# f401ccu6_w25q64_20210612.net
KiCad netlist of a schematic drawn in Altium Designer
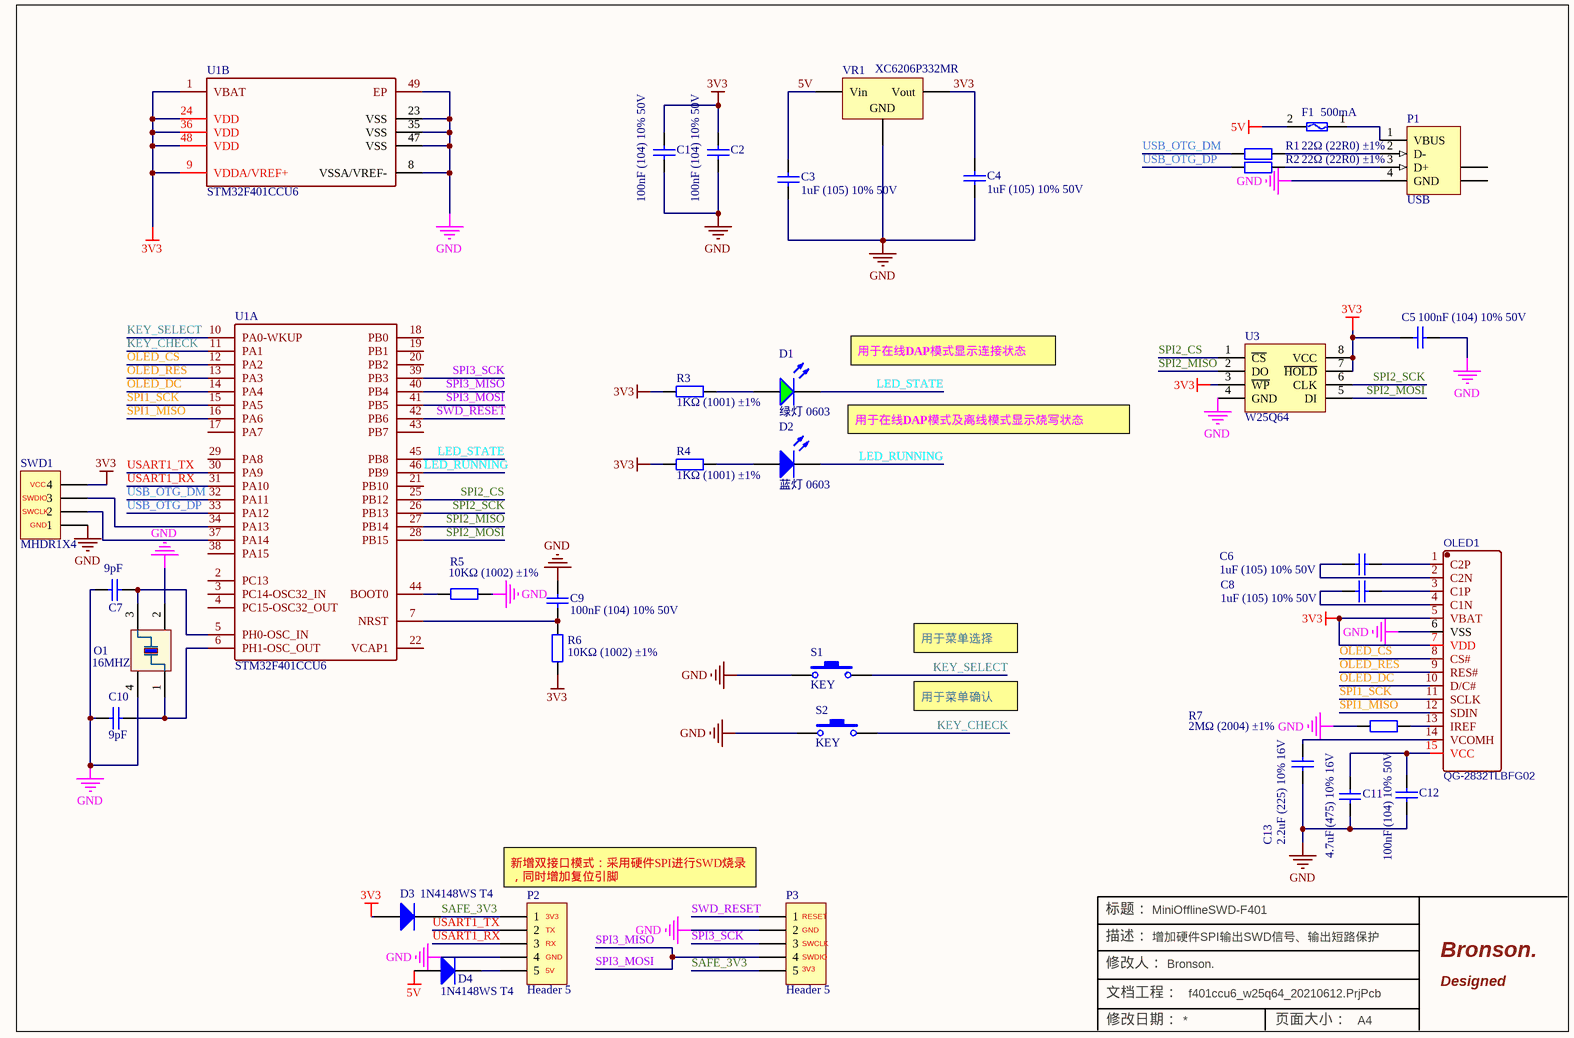
[diagram p0: f401ccu6_w25q64_20210612.SchDoc]

(export (version "E")
  (design (tool "Eeschema 10.0.6"))
  (components
    (comp (ref "C1")
      (value "100nF (104) 10% 50V")
      (footprint "pcblib201812:0805L")
      (description "贴片电容")
      (libsource (lib "Miscellaneous Devices LC") (part "0603 100nF (104) 10% 50V"))
    )
    (comp (ref "C2")
      (value "100nF (104) 10% 50V")
      (footprint "C0603")
      (description "贴片电容")
      (libsource (lib "Miscellaneous Devices LC") (part "0603 100nF (104) 10% 50V"))
    )
    (comp (ref "C3")
      (value "1uF (105) 10% 50V")
      (footprint "pcblib201812:0805L")
      (description "贴片电容")
      (libsource (lib "Miscellaneous Devices LC") (part "0603 1uF (105) 10% 50V"))
    )
    (comp (ref "C4")
      (value "1uF (105) 10% 50V")
      (footprint "pcblib201812:C0603")
      (description "贴片电容")
      (libsource (lib "Miscellaneous Devices LC") (part "0603 1uF (105) 10% 50V"))
    )
    (comp (ref "C5")
      (value "100nF (104) 10% 50V")
      (footprint "pcblib201812:C0603")
      (description "贴片电容")
      (libsource (lib "Miscellaneous Devices LC") (part "0603 100nF (104) 10% 50V"))
    )
    (comp (ref "C6")
      (value "1uF (105) 10% 50V")
      (footprint "pcblib201812:C0603")
      (description "贴片电容")
      (libsource (lib "Miscellaneous Devices LC") (part "0603 1uF (105) 10% 50V"))
    )
    (comp (ref "C7")
      (value "9pF")
      (footprint "pcblib201812:C0603")
      (description "贴片电容")
      (libsource (lib "Miscellaneous Devices LC") (part "0603 22pF (220) 5% 50V"))
    )
    (comp (ref "C8")
      (value "1uF (105) 10% 50V")
      (footprint "pcblib201812:C0603")
      (description "贴片电容")
      (libsource (lib "Miscellaneous Devices LC") (part "0603 1uF (105) 10% 50V"))
    )
    (comp (ref "C9")
      (value "100nF (104) 10% 50V")
      (footprint "pcblib201812:C0603")
      (description "贴片电容")
      (libsource (lib "Miscellaneous Devices LC") (part "0603 100nF (104) 10% 50V"))
    )
    (comp (ref "C10")
      (value "9pF")
      (footprint "pcblib201812:C0603")
      (description "贴片电容")
      (libsource (lib "Miscellaneous Devices LC") (part "0603 22pF (220) 5% 50V"))
    )
    (comp (ref "C11")
      (value "4.7uF (475) 10% 16V")
      (footprint "pcblib201812:C0603")
      (description "贴片电容")
      (libsource (lib "Miscellaneous Devices LC") (part "0603 4.7uF (475) 10% 16V"))
    )
    (comp (ref "C12")
      (value "100nF (104) 10% 50V")
      (footprint "pcblib201812:C0603")
      (description "贴片电容")
      (libsource (lib "Miscellaneous Devices LC") (part "0603 100nF (104) 10% 50V"))
    )
    (comp (ref "C13")
      (value "2.2uF (225) 10% 16V")
      (footprint "pcblib201812:C0603")
      (description "贴片电容")
      (libsource (lib "Miscellaneous Devices LC") (part "0603 2.2uF (225) 10% 16V"))
    )
    (comp (ref "D1")
      (value "绿灯 0603")
      (footprint "pcblib201812:LED_0603_GREEN")
      (description "发光二极管")
      (libsource (lib "Miscellaneous Devices LC") (part "0603 绿灯"))
    )
    (comp (ref "D2")
      (value "蓝灯 0603")
      (footprint "pcblib201812:LED_0603_BLUE")
      (description "发光二极管")
      (libsource (lib "Miscellaneous Devices LC") (part "0603 蓝灯"))
    )
    (comp (ref "D3")
      (value "1N4148WS T4")
      (footprint "SOD-323")
      (description "二极管")
      (libsource (lib "Miscellaneous Devices LC") (part "SOD-323 1N4148WS T4"))
    )
    (comp (ref "D4")
      (value "1N4148WS T4")
      (footprint "SOD-323")
      (description "二极管")
      (libsource (lib "Miscellaneous Devices LC") (part "SOD-323 1N4148WS T4"))
    )
    (comp (ref "F1")
      (value "500mA")
      (footprint "0603")
      (description "保险丝，熔断丝")
      (libsource (lib "Free Documents") (part "FUSE"))
    )
    (comp (ref "O1")
      (value "16MHZ")
      (footprint "pcblib201812:OSC 3225-4P")
      (description "OSC")
      (libsource (lib "altium-import") (part "root_1_OSC_"))
    )
    (comp (ref "OLED1")
      (value "QG-2832TLBFG02")
      (footprint "0.91-OLED")
      (fields (field (name "BOM_SUPPLIER PART") "C91220") (field (name "CONTRIBUTOR") "LCSC"))
      (libsource (lib "0.91-oled") (part "0.91-OLED"))
    )
    (comp (ref "P1")
      (value "USB")
      (footprint "f103ret6_w25q64_20200910:USB_A/P_B")
      (description "USB 1.1, Right Angle, SMT, A Type, Plug, 4 Position, Natural")
      (fields (field (name "PUBLISHER") "Altium Limited"))
      (libsource (lib "AMP Serial Bus USB") (part "1470695-2"))
    )
    (comp (ref "P2")
      (value "Header 5")
      (footprint "5PinHeader:PinHeader_5")
      (description "Header, 5-Pin")
      (fields (field (name "PUBLISHER") "Altium Limited"))
      (libsource (lib "Miscellaneous Connectors") (part "Header 5"))
    )
    (comp (ref "P3")
      (value "Header 5")
      (footprint "5PinHeader:PinHeader_5")
      (description "Header, 5-Pin")
      (fields (field (name "PUBLISHER") "Altium Limited"))
      (libsource (lib "Miscellaneous Connectors") (part "Header 5"))
    )
    (comp (ref "R1")
      (value "22Ω (22R0) ±1%")
      (footprint "pcblib201812:RES0603")
      (description "贴片电阻")
      (libsource (lib "Miscellaneous Devices LC") (part "0603 22Ω (22R0) 1%"))
    )
    (comp (ref "R2")
      (value "22Ω (22R0) ±1%")
      (footprint "pcblib201812:RES0603")
      (description "贴片电阻")
      (libsource (lib "Miscellaneous Devices LC") (part "0603 22Ω (22R0) 1%"))
    )
    (comp (ref "R3")
      (value "1KΩ (1001) ±1%")
      (footprint "pcblib201812:RES0603")
      (description "贴片电阻")
      (libsource (lib "Miscellaneous Devices LC") (part "0603 1KΩ (1001) 1%"))
    )
    (comp (ref "R4")
      (value "1KΩ (1001) ±1%")
      (footprint "pcblib201812:RES0603")
      (description "贴片电阻")
      (libsource (lib "Miscellaneous Devices LC") (part "0603 1KΩ (1001) 1%"))
    )
    (comp (ref "R5")
      (value "10KΩ (1002) ±1%")
      (footprint "pcblib201812:RES0603")
      (description "贴片电阻")
      (libsource (lib "") (part "0603 10KΩ (1002) 1%_1"))
    )
    (comp (ref "R6")
      (value "10KΩ (1002) ±1%")
      (footprint "pcblib201812:RES0603")
      (description "贴片电阻")
      (libsource (lib "Miscellaneous Devices LC") (part "0603 10KΩ (1002) 1%"))
    )
    (comp (ref "R7")
      (value "2MΩ (2004) ±1%")
      (footprint "pcblib201812:RES0603")
      (description "贴片电阻")
      (libsource (lib "Miscellaneous Devices LC") (part "0603 2MΩ (2004) 1%"))
    )
    (comp (ref "S1") (value "KEY") (footprint "KEY") (libsource (lib "altium-import") (part "root_0_KEY_")))
    (comp (ref "S2") (value "KEY") (footprint "KEY") (libsource (lib "altium-import") (part "root_0_KEY_")))
    (comp (ref "SWD1")
      (value "MHDR1X4")
      (footprint "MHDR1X4")
      (description "Header, 4-Pin")
      (fields (field (name "PUBLISHER") "Altium Limited"))
      (libsource (lib "Miscellaneous Connectors") (part "MHDR1X4"))
    )
    (comp (ref "U1")
      (value "STM32F401CCU6")
      (footprint "UFQFPN-48_L7.0-W7.0-P0.50-BL-EP")
      (libsource (lib "stm32f401ccu6") (part "STM32F401CCU6"))
    )
    (comp (ref "U3")
      (value "W25Q64")
      (footprint "f103ret6_w25q64_20200910:SOP8_W")
      (description "W25Q")
      (libsource (lib "Free Documents") (part "W25Q"))
    )
    (comp (ref "VR1")
      (value "XC6206P332MR")
      (footprint "SOT-23-3L")
      (description "低压差线性稳压(LDO)")
      (libsource (lib "Miscellaneous Devices LC") (part "SOT-23 XC6206P332MR"))
    )
  )
  (nets
    (net (code "1") (name "/KEY_CHECK") (class "Default")
      (node (ref "S2") (pin "2") (pinfunction "2_2") (pintype "power_in"))
      (node (ref "U1") (pin "11") (pinfunction "PA1_11") (pintype "passive"))
    )
    (net (code "2") (name "/KEY_SELECT") (class "Default")
      (node (ref "S1") (pin "2") (pinfunction "2_2") (pintype "power_in"))
      (node (ref "U1") (pin "10") (pinfunction "PA0-WKUP_10") (pintype "passive"))
    )
    (net (code "3") (name "/LED_RUNNING") (class "Default")
      (node (ref "D2") (pin "1") (pinfunction "1_1") (pintype "passive"))
      (node (ref "U1") (pin "46") (pinfunction "PB9_46") (pintype "passive"))
    )
    (net (code "4") (name "/LED_STATE") (class "Default")
      (node (ref "D1") (pin "1") (pinfunction "1_1") (pintype "passive"))
      (node (ref "U1") (pin "45") (pinfunction "PB8_45") (pintype "passive"))
    )
    (net (code "5") (name "/OLED_CS") (class "Default")
      (node (ref "OLED1") (pin "8") (pinfunction "CS#_8") (pintype "passive"))
      (node (ref "U1") (pin "12") (pinfunction "PA2_12") (pintype "passive"))
    )
    (net (code "6") (name "/OLED_DC") (class "Default")
      (node (ref "OLED1") (pin "10") (pinfunction "D/C#_10") (pintype "passive"))
      (node (ref "U1") (pin "14") (pinfunction "PA4_14") (pintype "passive"))
    )
    (net (code "7") (name "/OLED_RES") (class "Default")
      (node (ref "OLED1") (pin "9") (pinfunction "RES#_9") (pintype "passive"))
      (node (ref "U1") (pin "13") (pinfunction "PA3_13") (pintype "passive"))
    )
    (net (code "8") (name "/SAFE_3V3") (class "Default")
      (node (ref "D3") (pin "2") (pinfunction "K_2") (pintype "passive"))
      (node (ref "P2") (pin "1") (pinfunction "1_1") (pintype "passive"))
      (node (ref "P3") (pin "5") (pinfunction "5_5") (pintype "passive"))
    )
    (net (code "9") (name "/SPI1_MISO") (class "Default")
      (node (ref "OLED1") (pin "12") (pinfunction "SDIN_12") (pintype "passive"))
      (node (ref "U1") (pin "16") (pinfunction "PA6_16") (pintype "passive"))
    )
    (net (code "10") (name "/SPI1_SCK") (class "Default")
      (node (ref "OLED1") (pin "11") (pinfunction "SCLK_11") (pintype "passive"))
      (node (ref "U1") (pin "15") (pinfunction "PA5_15") (pintype "passive"))
    )
    (net (code "11") (name "/SPI2_CS") (class "Default")
      (node (ref "U1") (pin "25") (pinfunction "PB12_25") (pintype "passive"))
      (node (ref "U3") (pin "1") (pinfunction "~{CS}_1") (pintype "passive"))
    )
    (net (code "12") (name "/SPI2_MISO") (class "Default")
      (node (ref "U1") (pin "27") (pinfunction "PB14_27") (pintype "passive"))
      (node (ref "U3") (pin "2") (pinfunction "DO_2") (pintype "passive"))
    )
    (net (code "13") (name "/SPI2_MOSI") (class "Default")
      (node (ref "U1") (pin "28") (pinfunction "PB15_28") (pintype "passive"))
      (node (ref "U3") (pin "5") (pinfunction "DI_5") (pintype "passive"))
    )
    (net (code "14") (name "/SPI2_SCK") (class "Default")
      (node (ref "U1") (pin "26") (pinfunction "PB13_26") (pintype "passive"))
      (node (ref "U3") (pin "6") (pinfunction "CLK_6") (pintype "passive"))
    )
    (net (code "15") (name "/SPI3_MISO") (class "Default")
      (node (ref "P3") (pin "4") (pinfunction "4_4") (pintype "passive"))
      (node (ref "U1") (pin "40") (pinfunction "PB4_40") (pintype "passive"))
      (node (ref "U1") (pin "41") (pinfunction "PB5_41") (pintype "passive"))
    )
    (net (code "16") (name "/SPI3_SCK") (class "Default")
      (node (ref "P3") (pin "3") (pinfunction "3_3") (pintype "passive"))
      (node (ref "U1") (pin "39") (pinfunction "PB3_39") (pintype "passive"))
    )
    (net (code "17") (name "/SWD_RESET") (class "Default")
      (node (ref "P3") (pin "1") (pinfunction "1_1") (pintype "passive"))
      (node (ref "U1") (pin "42") (pinfunction "PB6_42") (pintype "passive"))
    )
    (net (code "18") (name "/USART1_RX") (class "Default")
      (node (ref "P2") (pin "3") (pinfunction "3_3") (pintype "passive"))
      (node (ref "U1") (pin "31") (pinfunction "PA10_31") (pintype "passive"))
    )
    (net (code "19") (name "/USART1_TX") (class "Default")
      (node (ref "P2") (pin "2") (pinfunction "2_2") (pintype "passive"))
      (node (ref "U1") (pin "30") (pinfunction "PA9_30") (pintype "passive"))
    )
    (net (code "20") (name "/USB_OTG_DM") (class "Default")
      (node (ref "R1") (pin "1") (pinfunction "1_1") (pintype "passive"))
      (node (ref "U1") (pin "32") (pinfunction "PA11_32") (pintype "passive"))
    )
    (net (code "21") (name "/USB_OTG_DP") (class "Default")
      (node (ref "R2") (pin "1") (pinfunction "1_1") (pintype "passive"))
      (node (ref "U1") (pin "33") (pinfunction "PA12_33") (pintype "passive"))
    )
    (net (code "22") (name "3V3") (class "Default")
      (node (ref "C1") (pin "2") (pinfunction "2_2") (pintype "passive"))
      (node (ref "C2") (pin "2") (pinfunction "2_2") (pintype "passive"))
      (node (ref "C4") (pin "2") (pinfunction "2_2") (pintype "passive"))
      (node (ref "C5") (pin "1") (pinfunction "1_1") (pintype "passive"))
      (node (ref "D3") (pin "1") (pinfunction "A_1") (pintype "passive"))
      (node (ref "OLED1") (pin "5") (pinfunction "VBAT_5") (pintype "passive"))
      (node (ref "OLED1") (pin "7") (pinfunction "VDD_7") (pintype "passive"))
      (node (ref "R3") (pin "2") (pinfunction "2_2") (pintype "passive"))
      (node (ref "R4") (pin "2") (pinfunction "2_2") (pintype "passive"))
      (node (ref "R6") (pin "2") (pinfunction "2_2") (pintype "passive"))
      (node (ref "SWD1") (pin "4") (pinfunction "4_4") (pintype "passive"))
      (node (ref "U1") (pin "1") (pinfunction "VBAT_1") (pintype "passive"))
      (node (ref "U1") (pin "24") (pinfunction "VDD_24") (pintype "passive"))
      (node (ref "U1") (pin "36") (pinfunction "VDD_36") (pintype "passive"))
      (node (ref "U1") (pin "48") (pinfunction "VDD_48") (pintype "passive"))
      (node (ref "U1") (pin "9") (pinfunction "VDDA/VREF+_9") (pintype "passive"))
      (node (ref "U3") (pin "3") (pinfunction "~{WP}_3") (pintype "passive"))
      (node (ref "U3") (pin "7") (pinfunction "~{HOLD}_7") (pintype "passive"))
      (node (ref "U3") (pin "8") (pinfunction "VCC_8") (pintype "passive"))
      (node (ref "VR1") (pin "2") (pinfunction "Vout_2") (pintype "passive"))
    )
    (net (code "23") (name "5V") (class "Default")
      (node (ref "C3") (pin "2") (pinfunction "2_2") (pintype "passive"))
      (node (ref "D4") (pin "1") (pinfunction "A_1") (pintype "passive"))
      (node (ref "F1") (pin "2") (pinfunction "5_2") (pintype "passive"))
      (node (ref "VR1") (pin "3") (pinfunction "Vin_3") (pintype "passive"))
    )
    (net (code "24") (name "GND") (class "Default")
      (node (ref "C1") (pin "1") (pinfunction "1_1") (pintype "passive"))
      (node (ref "C10") (pin "2") (pinfunction "2_2") (pintype "passive"))
      (node (ref "C11") (pin "1") (pinfunction "1_1") (pintype "passive"))
      (node (ref "C12") (pin "1") (pinfunction "1_1") (pintype "passive"))
      (node (ref "C13") (pin "1") (pinfunction "1_1") (pintype "passive"))
      (node (ref "C2") (pin "1") (pinfunction "1_1") (pintype "passive"))
      (node (ref "C3") (pin "1") (pinfunction "1_1") (pintype "passive"))
      (node (ref "C4") (pin "1") (pinfunction "1_1") (pintype "passive"))
      (node (ref "C5") (pin "2") (pinfunction "2_2") (pintype "passive"))
      (node (ref "C7") (pin "2") (pinfunction "2_2") (pintype "passive"))
      (node (ref "C9") (pin "1") (pinfunction "1_1") (pintype "passive"))
      (node (ref "O1") (pin "2") (pintype "passive"))
      (node (ref "O1") (pin "4") (pintype "passive"))
      (node (ref "OLED1") (pin "6") (pinfunction "VSS_6") (pintype "passive"))
      (node (ref "P1") (pin "4") (pinfunction "GND_4") (pintype "power_in"))
      (node (ref "P2") (pin "4") (pinfunction "4_4") (pintype "passive"))
      (node (ref "P3") (pin "2") (pinfunction "2_2") (pintype "passive"))
      (node (ref "R5") (pin "1") (pinfunction "1_1") (pintype "passive"))
      (node (ref "R7") (pin "1") (pinfunction "1_1") (pintype "passive"))
      (node (ref "S1") (pin "1") (pinfunction "1_1") (pintype "power_in"))
      (node (ref "S2") (pin "1") (pinfunction "1_1") (pintype "power_in"))
      (node (ref "SWD1") (pin "1") (pinfunction "1_1") (pintype "passive"))
      (node (ref "U1") (pin "23") (pinfunction "VSS_23") (pintype "passive"))
      (node (ref "U1") (pin "35") (pinfunction "VSS_35") (pintype "passive"))
      (node (ref "U1") (pin "47") (pinfunction "VSS_47") (pintype "passive"))
      (node (ref "U1") (pin "49") (pinfunction "EP_49") (pintype "passive"))
      (node (ref "U1") (pin "8") (pinfunction "VSSA/VREF-_8") (pintype "passive"))
      (node (ref "U3") (pin "4") (pinfunction "GND_4") (pintype "passive"))
      (node (ref "VR1") (pin "1") (pinfunction "GND_1") (pintype "passive"))
    )
    (net (code "25") (name "Net-(D1-Pad2)") (class "Default")
      (node (ref "D1") (pin "2") (pinfunction "2_2") (pintype "passive"))
      (node (ref "R3") (pin "1") (pinfunction "1_1") (pintype "passive"))
    )
    (net (code "26") (name "Net-(D2-Pad2)") (class "Default")
      (node (ref "D2") (pin "2") (pinfunction "2_2") (pintype "passive"))
      (node (ref "R4") (pin "1") (pinfunction "1_1") (pintype "passive"))
    )
    (net (code "27") (name "Net-(D4-K)") (class "Default")
      (node (ref "D4") (pin "2") (pinfunction "K_2") (pintype "passive"))
      (node (ref "P2") (pin "5") (pinfunction "5_5") (pintype "passive"))
    )
    (net (code "28") (name "Net-(F1-4)") (class "Default")
      (node (ref "F1") (pin "1") (pinfunction "4_1") (pintype "passive"))
      (node (ref "P1") (pin "1") (pinfunction "VBUS_1") (pintype "power_in"))
    )
    (net (code "29") (name "Net-(OLED1-C1N)") (class "Default")
      (node (ref "C8") (pin "1") (pinfunction "1_1") (pintype "passive"))
      (node (ref "OLED1") (pin "4") (pinfunction "C1N_4") (pintype "passive"))
    )
    (net (code "30") (name "Net-(OLED1-C1P)") (class "Default")
      (node (ref "C8") (pin "2") (pinfunction "2_2") (pintype "passive"))
      (node (ref "OLED1") (pin "3") (pinfunction "C1P_3") (pintype "passive"))
    )
    (net (code "31") (name "Net-(OLED1-C2N)") (class "Default")
      (node (ref "C6") (pin "1") (pinfunction "1_1") (pintype "passive"))
      (node (ref "OLED1") (pin "2") (pinfunction "C2N_2") (pintype "passive"))
    )
    (net (code "32") (name "Net-(OLED1-C2P)") (class "Default")
      (node (ref "C6") (pin "2") (pinfunction "2_2") (pintype "passive"))
      (node (ref "OLED1") (pin "1") (pinfunction "C2P_1") (pintype "passive"))
    )
    (net (code "33") (name "Net-(OLED1-IREF)") (class "Default")
      (node (ref "OLED1") (pin "13") (pinfunction "IREF_13") (pintype "passive"))
      (node (ref "R7") (pin "2") (pinfunction "2_2") (pintype "passive"))
    )
    (net (code "34") (name "Net-(OLED1-VCC)") (class "Default")
      (node (ref "C11") (pin "2") (pinfunction "2_2") (pintype "passive"))
      (node (ref "C12") (pin "2") (pinfunction "2_2") (pintype "passive"))
      (node (ref "OLED1") (pin "15") (pinfunction "VCC_15") (pintype "passive"))
    )
    (net (code "35") (name "Net-(OLED1-VCOMH)") (class "Default")
      (node (ref "C13") (pin "2") (pinfunction "2_2") (pintype "passive"))
      (node (ref "OLED1") (pin "14") (pinfunction "VCOMH_14") (pintype "passive"))
    )
    (net (code "36") (name "Net-(P1-D+)") (class "Default")
      (node (ref "P1") (pin "3") (pinfunction "D+_3") (pintype "input"))
      (node (ref "R2") (pin "2") (pinfunction "2_2") (pintype "passive"))
    )
    (net (code "37") (name "Net-(P1-D-)") (class "Default")
      (node (ref "P1") (pin "2") (pinfunction "D-_2") (pintype "input"))
      (node (ref "R1") (pin "2") (pinfunction "2_2") (pintype "passive"))
    )
    (net (code "38") (name "Net-(U1A-BOOT0)") (class "Default")
      (node (ref "R5") (pin "2") (pinfunction "2_2") (pintype "passive"))
      (node (ref "U1") (pin "44") (pinfunction "BOOT0_44") (pintype "passive"))
    )
    (net (code "39") (name "Net-(U1A-NRST)") (class "Default")
      (node (ref "C9") (pin "2") (pinfunction "2_2") (pintype "passive"))
      (node (ref "R6") (pin "1") (pinfunction "1_1") (pintype "passive"))
      (node (ref "U1") (pin "7") (pinfunction "NRST_7") (pintype "passive"))
    )
    (net (code "40") (name "Net-(U1A-PA13)") (class "Default")
      (node (ref "SWD1") (pin "3") (pinfunction "3_3") (pintype "passive"))
      (node (ref "U1") (pin "34") (pinfunction "PA13_34") (pintype "passive"))
    )
    (net (code "41") (name "Net-(U1A-PA14)") (class "Default")
      (node (ref "SWD1") (pin "2") (pinfunction "2_2") (pintype "passive"))
      (node (ref "U1") (pin "37") (pinfunction "PA14_37") (pintype "passive"))
    )
    (net (code "42") (name "Net-(U1A-PH0-OSC_IN)") (class "Default")
      (node (ref "C7") (pin "1") (pinfunction "1_1") (pintype "passive"))
      (node (ref "O1") (pin "3") (pintype "passive"))
      (node (ref "U1") (pin "5") (pinfunction "PH0-OSC_IN_5") (pintype "passive"))
    )
    (net (code "43") (name "Net-(U1A-PH1-OSC_OUT)") (class "Default")
      (node (ref "C10") (pin "1") (pinfunction "1_1") (pintype "passive"))
      (node (ref "O1") (pin "1") (pintype "passive"))
      (node (ref "U1") (pin "6") (pinfunction "PH1-OSC_OUT_6") (pintype "passive"))
    )
    (net (code "44") (name "unconnected-(P1-SHLD-Pad5)") (class "Default")
      (node (ref "P1") (pin "5") (pinfunction "SHLD_5") (pintype "passive"))
    )
    (net (code "45") (name "unconnected-(P1-SHLD-Pad6)") (class "Default")
      (node (ref "P1") (pin "6") (pinfunction "SHLD_6") (pintype "passive"))
    )
    (net (code "46") (name "unconnected-(U1A-PA7-Pad17)") (class "Default")
      (node (ref "U1") (pin "17") (pinfunction "PA7_17") (pintype "passive"))
    )
    (net (code "47") (name "unconnected-(U1A-PA8-Pad29)") (class "Default")
      (node (ref "U1") (pin "29") (pinfunction "PA8_29") (pintype "passive"))
    )
    (net (code "48") (name "unconnected-(U1A-PA15-Pad38)") (class "Default")
      (node (ref "U1") (pin "38") (pinfunction "PA15_38") (pintype "passive"))
    )
    (net (code "49") (name "unconnected-(U1A-PB0-Pad18)") (class "Default")
      (node (ref "U1") (pin "18") (pinfunction "PB0_18") (pintype "passive"))
    )
    (net (code "50") (name "unconnected-(U1A-PB1-Pad19)") (class "Default")
      (node (ref "U1") (pin "19") (pinfunction "PB1_19") (pintype "passive"))
    )
    (net (code "51") (name "unconnected-(U1A-PB2-Pad20)") (class "Default")
      (node (ref "U1") (pin "20") (pinfunction "PB2_20") (pintype "passive"))
    )
    (net (code "52") (name "unconnected-(U1A-PB7-Pad43)") (class "Default")
      (node (ref "U1") (pin "43") (pinfunction "PB7_43") (pintype "passive"))
    )
    (net (code "53") (name "unconnected-(U1A-PB10-Pad21)") (class "Default")
      (node (ref "U1") (pin "21") (pinfunction "PB10_21") (pintype "passive"))
    )
    (net (code "54") (name "unconnected-(U1A-PC13-Pad2)") (class "Default")
      (node (ref "U1") (pin "2") (pinfunction "PC13_2") (pintype "passive"))
    )
    (net (code "55") (name "unconnected-(U1A-PC14-OSC32_IN-Pad3)") (class "Default")
      (node (ref "U1") (pin "3") (pinfunction "PC14-OSC32_IN_3") (pintype "passive"))
    )
    (net (code "56") (name "unconnected-(U1A-PC15-OSC32_OUT-Pad4)") (class "Default")
      (node (ref "U1") (pin "4") (pinfunction "PC15-OSC32_OUT_4") (pintype "passive"))
    )
    (net (code "57") (name "unconnected-(U1A-VCAP1-Pad22)") (class "Default")
      (node (ref "U1") (pin "22") (pinfunction "VCAP1_22") (pintype "passive"))
    )
  )
)
